# MysensorsSensor.net
KiCad netlist of a schematic drawn in EAGLE
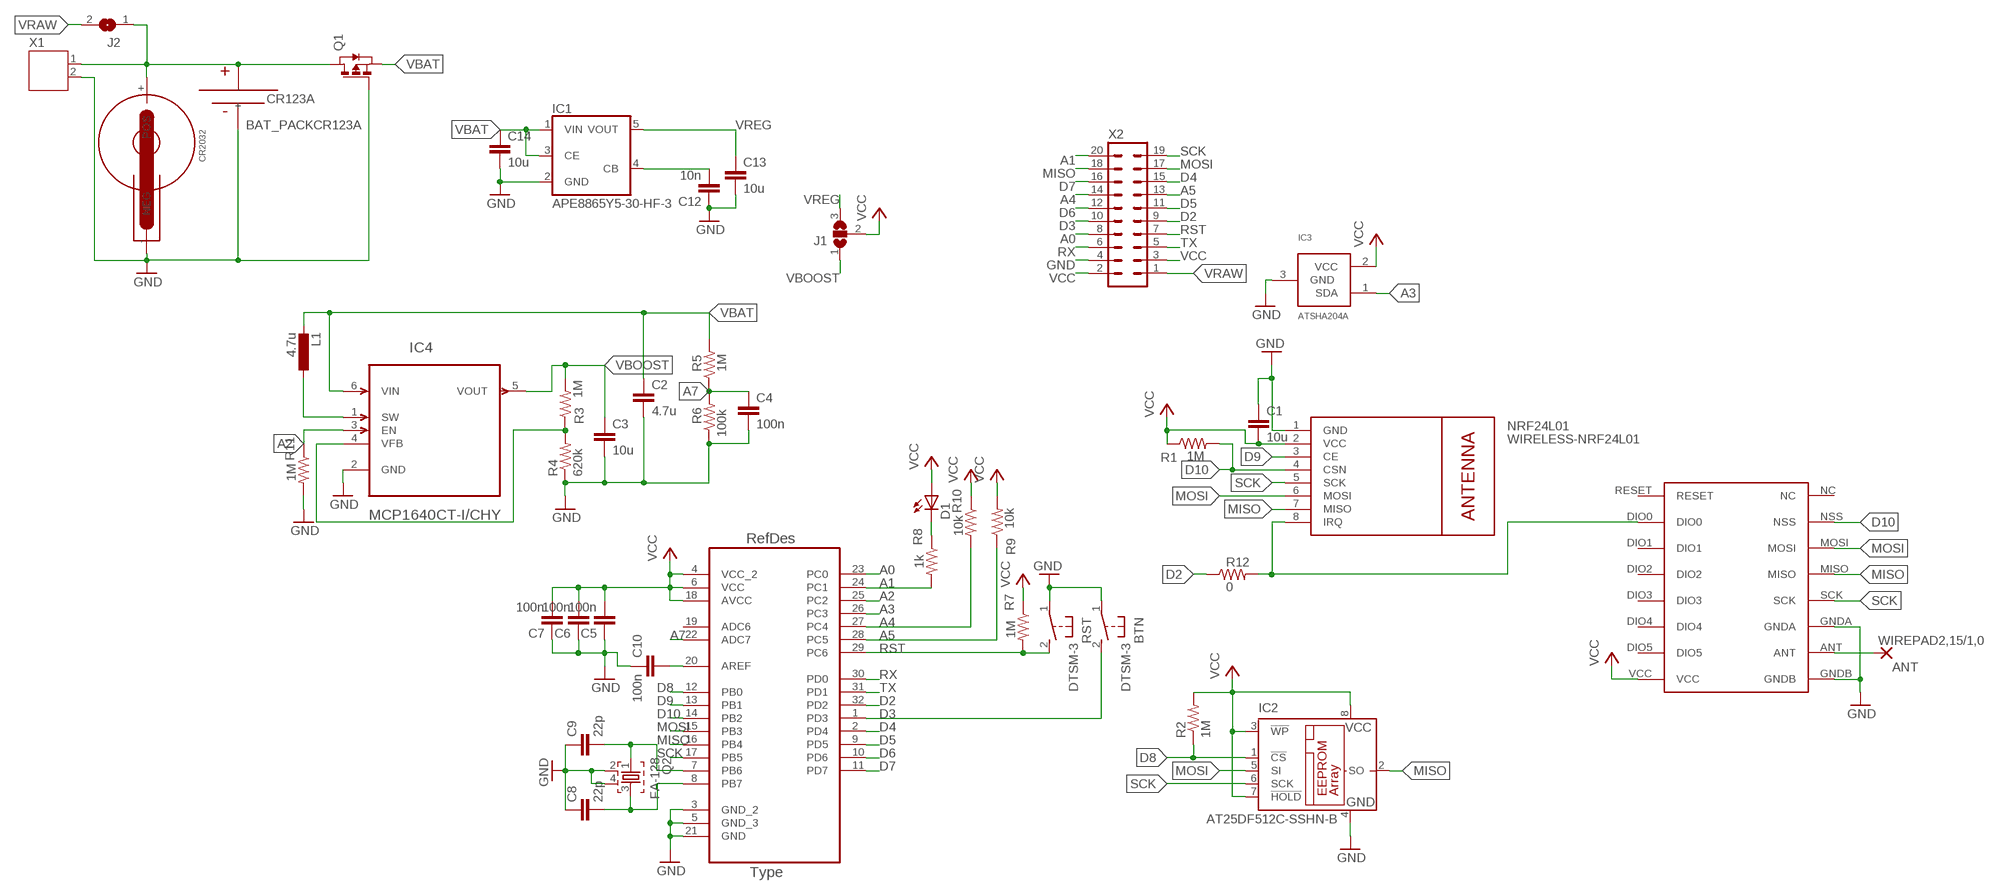
[diagram p0: schematic, sheet 1]

(export (version "E")
  (design (tool "Eeschema 10.0.6"))
  (components
    (comp (ref "ANT")
      (value "WIREPAD2,15/1,0")
      (footprint "eagle-import:2,15_1,0")
      (libsource (lib "eagle-import") (part "WIREPAD2,15/1,0"))
    )
    (comp (ref "BTN")
      (value "DTSM-3")
      (footprint "eagle-import:DTSM-3")
      (libsource (lib "eagle-import") (part "DTSM-3"))
    )
    (comp (ref "C1")
      (value "10u")
      (footprint "eagle-import:C0603K")
      (libsource (lib "eagle-import") (part "C-EUC0603K"))
    )
    (comp (ref "C2")
      (value "4.7u")
      (footprint "eagle-import:C0603K")
      (libsource (lib "eagle-import") (part "C-EUC0603K"))
    )
    (comp (ref "C3")
      (value "10u")
      (footprint "eagle-import:C0603K")
      (libsource (lib "eagle-import") (part "C-EUC0603K"))
    )
    (comp (ref "C4")
      (value "100n")
      (footprint "eagle-import:C0402")
      (libsource (lib "eagle-import") (part "C-EUC0402"))
    )
    (comp (ref "C5")
      (value "100n")
      (footprint "eagle-import:C0402")
      (libsource (lib "eagle-import") (part "C-EUC0402"))
    )
    (comp (ref "C6")
      (value "100n")
      (footprint "eagle-import:C0402")
      (libsource (lib "eagle-import") (part "C-EUC0402"))
    )
    (comp (ref "C7")
      (value "100n")
      (footprint "eagle-import:C0402")
      (libsource (lib "eagle-import") (part "C-EUC0402"))
    )
    (comp (ref "C8")
      (value "22p")
      (footprint "eagle-import:0402-CAP")
      (libsource (lib "eagle-import") (part "CAP0402-CAP"))
    )
    (comp (ref "C9")
      (value "22p")
      (footprint "eagle-import:0402-CAP")
      (libsource (lib "eagle-import") (part "CAP0402-CAP"))
    )
    (comp (ref "C10")
      (value "100n")
      (footprint "eagle-import:C0402")
      (libsource (lib "eagle-import") (part "C-EUC0402"))
    )
    (comp (ref "C12")
      (value "10n")
      (footprint "eagle-import:C0402")
      (libsource (lib "eagle-import") (part "C-EUC0402"))
    )
    (comp (ref "C13")
      (value "10u")
      (footprint "eagle-import:C0603K")
      (libsource (lib "eagle-import") (part "C-EUC0603K"))
    )
    (comp (ref "C14")
      (value "10u")
      (footprint "eagle-import:C0603K")
      (libsource (lib "eagle-import") (part "C-EUC0603K"))
    )
    (comp (ref "CR123A")
      (value "BAT_PACKCR123A")
      (footprint "eagle-import:BH123A")
      (fields (field (name "MANUFACTURER") "MPD") (field (name "MPN") "BH123A"))
      (libsource (lib "eagle-import") (part "BAT_PACKCR123A"))
    )
    (comp (ref "CR2032")
      (value "WA-BCPH_SMT_79527141")
      (footprint "eagle-import:79527141")
      (libsource (lib "eagle-import") (part "WA-BCPH_SMT_79527141"))
    )
    (comp (ref "D1")
      (value "LEDCHIP-LED0805")
      (footprint "eagle-import:CHIP-LED0805")
      (libsource (lib "eagle-import") (part "LEDCHIP-LED0805"))
    )
    (comp (ref "IC1")
      (value "APE8865Y5-30-HF-3")
      (footprint "eagle-import:SOT25")
      (libsource (lib "eagle-import") (part "TS5205"))
    )
    (comp (ref "IC2")
      (value "AT25DF512C-SSHN-B")
      (footprint "eagle-import:SO-08")
      (fields (field (name "MF") "MICROCHIP") (field (name "MPN") "25AA080/SN"))
      (libsource (lib "eagle-import") (part "25SNAA080"))
    )
    (comp (ref "IC3")
      (value "ATSHA204A")
      (footprint "eagle-import:SOT23")
      (libsource (lib "eagle-import") (part "ATSHA204A"))
    )
    (comp (ref "IC4")
      (value "MCP1640CT-I/CHY")
      (footprint "eagle-import:SOT95P270X145-6N")
      (libsource (lib "eagle-import") (part "MCP1640CT-I/CHY"))
    )
    (comp (ref "IC5")
      (value "ATMEGA328P-AU")
      (footprint "eagle-import:QFP80P900X900X120-32N")
      (libsource (lib "eagle-import") (part "ATMEGA328P-AU"))
    )
    (comp (ref "J1")
      (value "SJ2W")
      (footprint "eagle-import:SJ_2")
      (libsource (lib "eagle-import") (part "SJ2W"))
    )
    (comp (ref "J2") (value "SJ") (footprint "eagle-import:SJ") (libsource (lib "eagle-import") (part "SJ")))
    (comp (ref "L1")
      (value "4.7u")
      (footprint "eagle-import:L3225P")
      (libsource (lib "eagle-import") (part "L-EUL3225P"))
    )
    (comp (ref "NRF24L01")
      (value "WIRELESS-NRF24L01")
      (footprint "eagle-import:WIRELESS-NRF24L01")
      (libsource (lib "eagle-import") (part "WIRELESS-NRF24L01"))
    )
    (comp (ref "Q1")
      (value "PMOSSOT23")
      (footprint "eagle-import:SOT-23")
      (libsource (lib "eagle-import") (part "PMOSSOT23"))
    )
    (comp (ref "Q2")
      (value "FA-128")
      (footprint "eagle-import:FA-128")
      (libsource (lib "eagle-import") (part "FA-128"))
    )
    (comp (ref "R1")
      (value "1M")
      (footprint "eagle-import:R0603")
      (libsource (lib "eagle-import") (part "R-US_R0603"))
    )
    (comp (ref "R2")
      (value "1M")
      (footprint "eagle-import:R0603")
      (libsource (lib "eagle-import") (part "R-US_R0603"))
    )
    (comp (ref "R3")
      (value "1M")
      (footprint "eagle-import:R0603")
      (libsource (lib "eagle-import") (part "R-US_R0603"))
    )
    (comp (ref "R4")
      (value "620k")
      (footprint "eagle-import:R0603")
      (libsource (lib "eagle-import") (part "R-US_R0603"))
    )
    (comp (ref "R5")
      (value "1M")
      (footprint "eagle-import:0603-RES")
      (libsource (lib "eagle-import") (part "RESISTOR0603-RES"))
    )
    (comp (ref "R6")
      (value "100k")
      (footprint "eagle-import:0603-RES")
      (libsource (lib "eagle-import") (part "RESISTOR0603-RES"))
    )
    (comp (ref "R7")
      (value "1M")
      (footprint "eagle-import:R0603")
      (libsource (lib "eagle-import") (part "R-US_R0603"))
    )
    (comp (ref "R8")
      (value "1k")
      (footprint "eagle-import:R0603")
      (libsource (lib "eagle-import") (part "R-US_R0603"))
    )
    (comp (ref "R9")
      (value "10k")
      (footprint "eagle-import:R0603")
      (libsource (lib "eagle-import") (part "R-US_R0603"))
    )
    (comp (ref "R10")
      (value "10k")
      (footprint "eagle-import:R0603")
      (libsource (lib "eagle-import") (part "R-US_R0603"))
    )
    (comp (ref "R11")
      (value "1M")
      (footprint "eagle-import:R0603")
      (libsource (lib "eagle-import") (part "R-US_R0603"))
    )
    (comp (ref "R12")
      (value "0")
      (footprint "eagle-import:0603-RES")
      (libsource (lib "eagle-import") (part "RESISTOR0603-RES"))
    )
    (comp (ref "RFM69W")
      (value "RFM69HW")
      (footprint "eagle-import:RFM")
      (libsource (lib "eagle-import") (part "RFM69HW"))
    )
    (comp (ref "RST")
      (value "DTSM-3")
      (footprint "eagle-import:DTSM-3")
      (libsource (lib "eagle-import") (part "DTSM-3"))
    )
    (comp (ref "X1")
      (value "JST-PH2")
      (footprint "eagle-import:JST-PH2")
      (libsource (lib "eagle-import") (part "JST-PH2"))
    )
    (comp (ref "X2")
      (value "MA10-2")
      (footprint "eagle-import:MA10-2")
      (libsource (lib "eagle-import") (part "MA10-2"))
    )
  )
  (nets
    (net (code "1") (name "/A0") (class "Default")
      (node (ref "IC5") (pin "23") (pinfunction "PC0_23") (pintype "bidirectional"))
      (node (ref "X2") (pin "8") (pinfunction "8_8") (pintype "passive"))
    )
    (net (code "2") (name "/A1") (class "Default")
      (node (ref "IC5") (pin "24") (pinfunction "PC1_24") (pintype "bidirectional"))
      (node (ref "R8") (pin "2") (pinfunction "2_2") (pintype "passive"))
      (node (ref "X2") (pin "20") (pinfunction "20_20") (pintype "passive"))
    )
    (net (code "3") (name "/A4") (class "Default")
      (node (ref "IC5") (pin "27") (pinfunction "PC4_27") (pintype "bidirectional"))
      (node (ref "R10") (pin "2") (pinfunction "2_2") (pintype "passive"))
      (node (ref "X2") (pin "14") (pinfunction "14_14") (pintype "passive"))
    )
    (net (code "4") (name "/A5") (class "Default")
      (node (ref "IC5") (pin "28") (pinfunction "PC5_28") (pintype "bidirectional"))
      (node (ref "R9") (pin "1") (pinfunction "1_1") (pintype "passive"))
      (node (ref "X2") (pin "13") (pinfunction "13_13") (pintype "passive"))
    )
    (net (code "5") (name "/D3") (class "Default")
      (node (ref "BTN") (pin "2") (pinfunction "2_2") (pintype "passive"))
      (node (ref "IC5") (pin "1") (pinfunction "PD3_1") (pintype "bidirectional"))
      (node (ref "X2") (pin "10") (pinfunction "10_10") (pintype "passive"))
    )
    (net (code "6") (name "/D4") (class "Default")
      (node (ref "IC5") (pin "2") (pinfunction "PD4_2") (pintype "bidirectional"))
      (node (ref "X2") (pin "15") (pinfunction "15_15") (pintype "passive"))
    )
    (net (code "7") (name "/D5") (class "Default")
      (node (ref "IC5") (pin "9") (pinfunction "PD5_9") (pintype "bidirectional"))
      (node (ref "X2") (pin "11") (pinfunction "11_11") (pintype "passive"))
    )
    (net (code "8") (name "/D6") (class "Default")
      (node (ref "IC5") (pin "10") (pinfunction "PD6_10") (pintype "bidirectional"))
      (node (ref "X2") (pin "12") (pinfunction "12_12") (pintype "passive"))
    )
    (net (code "9") (name "/D7") (class "Default")
      (node (ref "IC5") (pin "11") (pinfunction "PD7_11") (pintype "bidirectional"))
      (node (ref "X2") (pin "16") (pinfunction "16_16") (pintype "passive"))
    )
    (net (code "10") (name "/RST") (class "Default")
      (node (ref "IC5") (pin "29") (pinfunction "PC6_29") (pintype "bidirectional"))
      (node (ref "R7") (pin "2") (pinfunction "2_2") (pintype "passive"))
      (node (ref "RST") (pin "2") (pinfunction "2_2") (pintype "passive"))
      (node (ref "X2") (pin "7") (pinfunction "7_7") (pintype "passive"))
    )
    (net (code "11") (name "/RX") (class "Default")
      (node (ref "IC5") (pin "30") (pinfunction "PD0_30") (pintype "bidirectional"))
      (node (ref "X2") (pin "6") (pinfunction "6_6") (pintype "passive"))
    )
    (net (code "12") (name "/TX") (class "Default")
      (node (ref "IC5") (pin "31") (pinfunction "PD1_31") (pintype "bidirectional"))
      (node (ref "X2") (pin "5") (pinfunction "5_5") (pintype "passive"))
    )
    (net (code "13") (name "/VREG") (class "Default")
      (node (ref "C13") (pin "1") (pinfunction "1_1") (pintype "passive"))
      (node (ref "IC1") (pin "5") (pinfunction "VOUT_5") (pintype "passive"))
      (node (ref "J1") (pin "3") (pinfunction "3_3") (pintype "passive"))
    )
    (net (code "14") (name "A2") (class "Default")
      (node (ref "IC4") (pin "3") (pinfunction "EN_3") (pintype "input"))
      (node (ref "IC5") (pin "25") (pinfunction "PC2_25") (pintype "bidirectional"))
      (node (ref "R11") (pin "1") (pinfunction "1_1") (pintype "passive"))
    )
    (net (code "15") (name "A3") (class "Default")
      (node (ref "IC3") (pin "1") (pinfunction "SDA_1") (pintype "bidirectional"))
      (node (ref "IC5") (pin "26") (pinfunction "PC3_26") (pintype "bidirectional"))
    )
    (net (code "16") (name "A7") (class "Default")
      (node (ref "C4") (pin "1") (pinfunction "1_1") (pintype "passive"))
      (node (ref "IC5") (pin "22") (pinfunction "ADC7_22") (pintype "input"))
      (node (ref "R5") (pin "1") (pinfunction "1_1") (pintype "passive"))
      (node (ref "R6") (pin "2") (pinfunction "2_2") (pintype "passive"))
    )
    (net (code "17") (name "D2") (class "Default")
      (node (ref "IC5") (pin "32") (pinfunction "PD2_32") (pintype "bidirectional"))
      (node (ref "R12") (pin "1") (pinfunction "1_1") (pintype "passive"))
      (node (ref "X2") (pin "9") (pinfunction "9_9") (pintype "passive"))
    )
    (net (code "18") (name "D8") (class "Default")
      (node (ref "IC2") (pin "1") (pinfunction "~{CS}_1") (pintype "input"))
      (node (ref "IC5") (pin "12") (pinfunction "PB0_12") (pintype "bidirectional"))
      (node (ref "R2") (pin "1") (pinfunction "1_1") (pintype "passive"))
    )
    (net (code "19") (name "D9") (class "Default")
      (node (ref "IC5") (pin "13") (pinfunction "PB1_13") (pintype "bidirectional"))
      (node (ref "NRF24L01") (pin "3") (pinfunction "CE_3") (pintype "bidirectional"))
    )
    (net (code "20") (name "D10") (class "Default")
      (node (ref "IC5") (pin "14") (pinfunction "PB2_14") (pintype "bidirectional"))
      (node (ref "NRF24L01") (pin "4") (pinfunction "CSN_4") (pintype "bidirectional"))
      (node (ref "R1") (pin "2") (pinfunction "2_2") (pintype "passive"))
      (node (ref "RFM69W") (pin "NSS") (pinfunction "NSS_NSS") (pintype "bidirectional"))
    )
    (net (code "21") (name "GND") (class "Default")
      (node (ref "BTN") (pin "1") (pinfunction "1_1") (pintype "passive"))
      (node (ref "C1") (pin "1") (pinfunction "1_1") (pintype "passive"))
      (node (ref "C10") (pin "2") (pinfunction "2_2") (pintype "passive"))
      (node (ref "C12") (pin "1") (pinfunction "1_1") (pintype "passive"))
      (node (ref "C13") (pin "2") (pinfunction "2_2") (pintype "passive"))
      (node (ref "C14") (pin "2") (pinfunction "2_2") (pintype "passive"))
      (node (ref "C2") (pin "2") (pinfunction "2_2") (pintype "passive"))
      (node (ref "C3") (pin "2") (pinfunction "2_2") (pintype "passive"))
      (node (ref "C4") (pin "2") (pinfunction "2_2") (pintype "passive"))
      (node (ref "C5") (pin "1") (pinfunction "1_1") (pintype "passive"))
      (node (ref "C6") (pin "1") (pinfunction "1_1") (pintype "passive"))
      (node (ref "C7") (pin "1") (pinfunction "1_1") (pintype "passive"))
      (node (ref "C8") (pin "1") (pinfunction "1_1") (pintype "passive"))
      (node (ref "C9") (pin "1") (pinfunction "1_1") (pintype "passive"))
      (node (ref "CR123A") (pin "-") (pinfunction "-_-") (pintype "bidirectional"))
      (node (ref "CR2032") (pin "-") (pinfunction "NEG_-") (pintype "bidirectional"))
      (node (ref "IC1") (pin "2") (pinfunction "GND_2") (pintype "passive"))
      (node (ref "IC2") (pin "4") (pinfunction "GND_4") (pintype "power_in"))
      (node (ref "IC3") (pin "3") (pinfunction "GND_3") (pintype "bidirectional"))
      (node (ref "IC4") (pin "2") (pinfunction "GND_2") (pintype "passive"))
      (node (ref "IC5") (pin "21") (pinfunction "GND_21") (pintype "passive"))
      (node (ref "IC5") (pin "3") (pinfunction "GND_2_3") (pintype "passive"))
      (node (ref "IC5") (pin "5") (pinfunction "GND_3_5") (pintype "passive"))
      (node (ref "NRF24L01") (pin "1") (pinfunction "GND_1") (pintype "power_in"))
      (node (ref "Q1") (pin "3") (pinfunction "G_3") (pintype "passive"))
      (node (ref "Q2") (pin "2") (pinfunction "2_2") (pintype "passive"))
      (node (ref "Q2") (pin "4") (pinfunction "4_4") (pintype "passive"))
      (node (ref "R11") (pin "2") (pinfunction "2_2") (pintype "passive"))
      (node (ref "R4") (pin "1") (pinfunction "1_1") (pintype "passive"))
      (node (ref "R6") (pin "1") (pinfunction "1_1") (pintype "passive"))
      (node (ref "RFM69W") (pin "GNDA") (pinfunction "GNDA_GNDA") (pintype "bidirectional"))
      (node (ref "RFM69W") (pin "GNDB") (pinfunction "GNDB_GNDB") (pintype "bidirectional"))
      (node (ref "RST") (pin "1") (pinfunction "1_1") (pintype "passive"))
      (node (ref "X1") (pin "2") (pinfunction "2_2") (pintype "passive"))
      (node (ref "X2") (pin "4") (pinfunction "4_4") (pintype "passive"))
    )
    (net (code "22") (name "MISO") (class "Default")
      (node (ref "IC2") (pin "2") (pinfunction "SO_2") (pintype "bidirectional"))
      (node (ref "IC5") (pin "16") (pinfunction "PB4_16") (pintype "bidirectional"))
      (node (ref "NRF24L01") (pin "7") (pinfunction "MISO_7") (pintype "bidirectional"))
      (node (ref "RFM69W") (pin "MISO") (pinfunction "MISO_MISO") (pintype "bidirectional"))
      (node (ref "X2") (pin "18") (pinfunction "18_18") (pintype "passive"))
    )
    (net (code "23") (name "MOSI") (class "Default")
      (node (ref "IC2") (pin "5") (pinfunction "SI_5") (pintype "input"))
      (node (ref "IC5") (pin "15") (pinfunction "PB3_15") (pintype "bidirectional"))
      (node (ref "NRF24L01") (pin "6") (pinfunction "MOSI_6") (pintype "bidirectional"))
      (node (ref "RFM69W") (pin "MOSI") (pinfunction "MOSI_MOSI") (pintype "bidirectional"))
      (node (ref "X2") (pin "17") (pinfunction "17_17") (pintype "passive"))
    )
    (net (code "24") (name "Net-(ANT-P)") (class "Default")
      (node (ref "ANT") (pin "1") (pinfunction "P_1") (pintype "passive"))
      (node (ref "RFM69W") (pin "ANT") (pinfunction "ANT_ANT") (pintype "bidirectional"))
    )
    (net (code "25") (name "Net-(CR2032-POS)") (class "Default")
      (node (ref "CR123A") (pin "+") (pinfunction "+_+") (pintype "bidirectional"))
      (node (ref "CR2032") (pin "+") (pinfunction "POS_+") (pintype "bidirectional"))
      (node (ref "J2") (pin "1") (pinfunction "1_1") (pintype "passive"))
      (node (ref "Q1") (pin "1") (pinfunction "D_1") (pintype "passive"))
      (node (ref "X1") (pin "1") (pinfunction "1_1") (pintype "passive"))
    )
    (net (code "26") (name "Net-(D1-PadC)") (class "Default")
      (node (ref "D1") (pin "C") (pinfunction "C_C") (pintype "passive"))
      (node (ref "R8") (pin "1") (pinfunction "1_1") (pintype "passive"))
    )
    (net (code "27") (name "Net-(IC1-CB)") (class "Default")
      (node (ref "C12") (pin "2") (pinfunction "2_2") (pintype "passive"))
      (node (ref "IC1") (pin "4") (pinfunction "CB_4") (pintype "input"))
    )
    (net (code "28") (name "Net-(IC4-SW)") (class "Default")
      (node (ref "IC4") (pin "1") (pinfunction "SW_1") (pintype "input"))
      (node (ref "L1") (pin "1") (pinfunction "1_1") (pintype "passive"))
    )
    (net (code "29") (name "Net-(IC4-VFB)") (class "Default")
      (node (ref "IC4") (pin "4") (pinfunction "VFB_4") (pintype "input"))
      (node (ref "R3") (pin "1") (pinfunction "1_1") (pintype "passive"))
      (node (ref "R4") (pin "2") (pinfunction "2_2") (pintype "passive"))
    )
    (net (code "30") (name "Net-(IC5-AREF)") (class "Default")
      (node (ref "C10") (pin "1") (pinfunction "1_1") (pintype "passive"))
      (node (ref "IC5") (pin "20") (pinfunction "AREF_20") (pintype "input"))
    )
    (net (code "31") (name "Net-(IC5-PB6)") (class "Default")
      (node (ref "C9") (pin "2") (pinfunction "2_2") (pintype "passive"))
      (node (ref "IC5") (pin "7") (pinfunction "PB6_7") (pintype "bidirectional"))
      (node (ref "Q2") (pin "1") (pinfunction "1_1") (pintype "passive"))
    )
    (net (code "32") (name "Net-(IC5-PB7)") (class "Default")
      (node (ref "C8") (pin "2") (pinfunction "2_2") (pintype "passive"))
      (node (ref "IC5") (pin "8") (pinfunction "PB7_8") (pintype "bidirectional"))
      (node (ref "Q2") (pin "3") (pinfunction "3_3") (pintype "passive"))
    )
    (net (code "33") (name "Net-(NRF24L01-IRQ)") (class "Default")
      (node (ref "NRF24L01") (pin "8") (pinfunction "IRQ_8") (pintype "bidirectional"))
      (node (ref "R12") (pin "2") (pinfunction "2_2") (pintype "passive"))
      (node (ref "RFM69W") (pin "DIO0") (pinfunction "DIO0_DIO0") (pintype "bidirectional"))
    )
    (net (code "34") (name "SCK") (class "Default")
      (node (ref "IC2") (pin "6") (pinfunction "SCK_6") (pintype "input"))
      (node (ref "IC5") (pin "17") (pinfunction "PB5_17") (pintype "bidirectional"))
      (node (ref "NRF24L01") (pin "5") (pinfunction "SCK_5") (pintype "bidirectional"))
      (node (ref "RFM69W") (pin "SCK") (pinfunction "SCK_SCK") (pintype "bidirectional"))
      (node (ref "X2") (pin "19") (pinfunction "19_19") (pintype "passive"))
    )
    (net (code "35") (name "VBAT") (class "Default")
      (node (ref "C14") (pin "1") (pinfunction "1_1") (pintype "passive"))
      (node (ref "C2") (pin "1") (pinfunction "1_1") (pintype "passive"))
      (node (ref "IC1") (pin "1") (pinfunction "VIN_1") (pintype "input"))
      (node (ref "IC1") (pin "3") (pinfunction "CE_3") (pintype "input"))
      (node (ref "IC4") (pin "6") (pinfunction "VIN_6") (pintype "input"))
      (node (ref "L1") (pin "2") (pinfunction "2_2") (pintype "passive"))
      (node (ref "Q1") (pin "2") (pinfunction "S_2") (pintype "passive"))
      (node (ref "R5") (pin "2") (pinfunction "2_2") (pintype "passive"))
    )
    (net (code "36") (name "VBOOST") (class "Default")
      (node (ref "C3") (pin "1") (pinfunction "1_1") (pintype "passive"))
      (node (ref "IC4") (pin "5") (pinfunction "VOUT_5") (pintype "output"))
      (node (ref "J1") (pin "1") (pinfunction "1_1") (pintype "passive"))
      (node (ref "R3") (pin "2") (pinfunction "2_2") (pintype "passive"))
    )
    (net (code "37") (name "VCC") (class "Default")
      (node (ref "C1") (pin "2") (pinfunction "2_2") (pintype "passive"))
      (node (ref "C5") (pin "2") (pinfunction "2_2") (pintype "passive"))
      (node (ref "C6") (pin "2") (pinfunction "2_2") (pintype "passive"))
      (node (ref "C7") (pin "2") (pinfunction "2_2") (pintype "passive"))
      (node (ref "D1") (pin "A") (pinfunction "A_A") (pintype "passive"))
      (node (ref "IC2") (pin "3") (pinfunction "~{WP}_3") (pintype "input"))
      (node (ref "IC2") (pin "7") (pinfunction "~{HOLD}_7") (pintype "input"))
      (node (ref "IC2") (pin "8") (pinfunction "VCC_8") (pintype "power_in"))
      (node (ref "IC3") (pin "2") (pinfunction "VCC_2") (pintype "bidirectional"))
      (node (ref "IC5") (pin "18") (pinfunction "AVCC_18") (pintype "power_in"))
      (node (ref "IC5") (pin "4") (pinfunction "VCC_2_4") (pintype "power_in"))
      (node (ref "IC5") (pin "6") (pinfunction "VCC_6") (pintype "power_in"))
      (node (ref "J1") (pin "2") (pinfunction "2_2") (pintype "passive"))
      (node (ref "NRF24L01") (pin "2") (pinfunction "VCC_2") (pintype "power_in"))
      (node (ref "R1") (pin "1") (pinfunction "1_1") (pintype "passive"))
      (node (ref "R10") (pin "1") (pinfunction "1_1") (pintype "passive"))
      (node (ref "R2") (pin "2") (pinfunction "2_2") (pintype "passive"))
      (node (ref "R7") (pin "1") (pinfunction "1_1") (pintype "passive"))
      (node (ref "R9") (pin "2") (pinfunction "2_2") (pintype "passive"))
      (node (ref "RFM69W") (pin "VCC") (pinfunction "VCC_VCC") (pintype "bidirectional"))
      (node (ref "X2") (pin "2") (pinfunction "2_2") (pintype "passive"))
      (node (ref "X2") (pin "3") (pinfunction "3_3") (pintype "passive"))
    )
    (net (code "38") (name "VRAW") (class "Default")
      (node (ref "J2") (pin "2") (pinfunction "2_2") (pintype "passive"))
      (node (ref "X2") (pin "1") (pinfunction "1_1") (pintype "passive"))
    )
    (net (code "39") (name "unconnected-(IC5-ADC6-Pad19)") (class "Default")
      (node (ref "IC5") (pin "19") (pinfunction "ADC6_19") (pintype "input"))
    )
    (net (code "40") (name "unconnected-(RFM69W-PadDIO1)") (class "Default")
      (node (ref "RFM69W") (pin "DIO1") (pinfunction "DIO1_DIO1") (pintype "bidirectional"))
    )
    (net (code "41") (name "unconnected-(RFM69W-PadDIO2)") (class "Default")
      (node (ref "RFM69W") (pin "DIO2") (pinfunction "DIO2_DIO2") (pintype "bidirectional"))
    )
    (net (code "42") (name "unconnected-(RFM69W-PadDIO3)") (class "Default")
      (node (ref "RFM69W") (pin "DIO3") (pinfunction "DIO3_DIO3") (pintype "bidirectional"))
    )
    (net (code "43") (name "unconnected-(RFM69W-PadDIO4)") (class "Default")
      (node (ref "RFM69W") (pin "DIO4") (pinfunction "DIO4_DIO4") (pintype "bidirectional"))
    )
    (net (code "44") (name "unconnected-(RFM69W-PadDIO5)") (class "Default")
      (node (ref "RFM69W") (pin "DIO5") (pinfunction "DIO5_DIO5") (pintype "bidirectional"))
    )
    (net (code "45") (name "unconnected-(RFM69W-PadNC)") (class "Default")
      (node (ref "RFM69W") (pin "NC") (pinfunction "NC_NC") (pintype "bidirectional"))
    )
    (net (code "46") (name "unconnected-(RFM69W-PadRESET)") (class "Default")
      (node (ref "RFM69W") (pin "RESET") (pinfunction "RESET_RESET") (pintype "bidirectional"))
    )
  )
)
